# d150_in8-2_rev_a.net
KiCad netlist of a schematic drawn in EAGLE
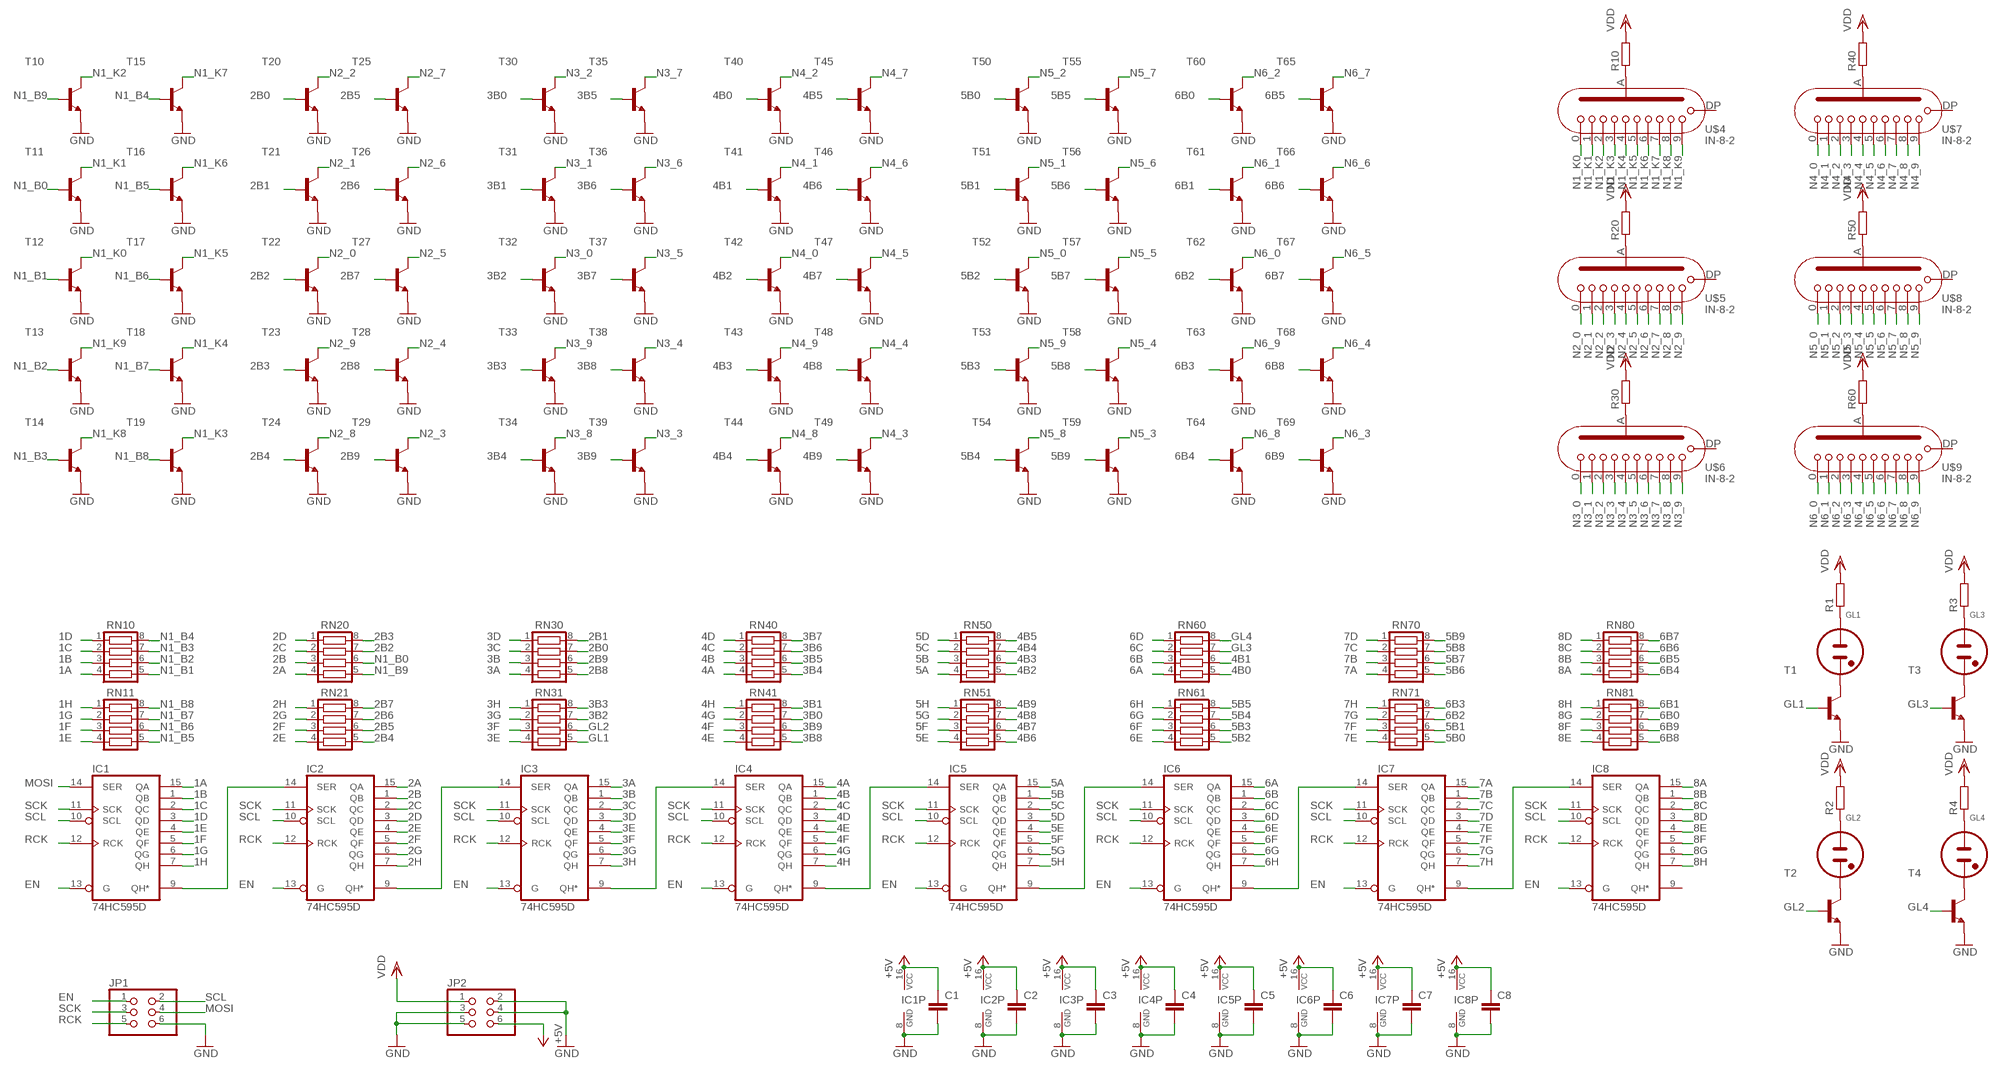
[diagram p0: schematic, sheet 1]

(export (version "E")
  (design (tool "Eeschema 10.0.6"))
  (components
    (comp (ref "C1")
      (value "C-EUC0603")
      (footprint "eagle-import:C0603")
      (libsource (lib "eagle-import") (part "C-EUC0603"))
    )
    (comp (ref "C2")
      (value "C-EUC0603")
      (footprint "eagle-import:C0603")
      (libsource (lib "eagle-import") (part "C-EUC0603"))
    )
    (comp (ref "C3")
      (value "C-EUC0603")
      (footprint "eagle-import:C0603")
      (libsource (lib "eagle-import") (part "C-EUC0603"))
    )
    (comp (ref "C4")
      (value "C-EUC0603")
      (footprint "eagle-import:C0603")
      (libsource (lib "eagle-import") (part "C-EUC0603"))
    )
    (comp (ref "C5")
      (value "C-EUC0603")
      (footprint "eagle-import:C0603")
      (libsource (lib "eagle-import") (part "C-EUC0603"))
    )
    (comp (ref "C6")
      (value "C-EUC0603")
      (footprint "eagle-import:C0603")
      (libsource (lib "eagle-import") (part "C-EUC0603"))
    )
    (comp (ref "C7")
      (value "C-EUC0603")
      (footprint "eagle-import:C0603")
      (libsource (lib "eagle-import") (part "C-EUC0603"))
    )
    (comp (ref "C8")
      (value "C-EUC0603")
      (footprint "eagle-import:C0603")
      (libsource (lib "eagle-import") (part "C-EUC0603"))
    )
    (comp (ref "GL1")
      (value "NE2-NEON-BULB-DRILL")
      (footprint "eagle-import:NE2-NEON-BULB-DRILL")
      (libsource (lib "eagle-import") (part "NE2-NEON-BULB-DRILL"))
    )
    (comp (ref "GL2")
      (value "NE2-NEON-BULB-DRILL")
      (footprint "eagle-import:NE2-NEON-BULB-DRILL")
      (libsource (lib "eagle-import") (part "NE2-NEON-BULB-DRILL"))
    )
    (comp (ref "GL3")
      (value "NE2-NEON-BULB-DRILL")
      (footprint "eagle-import:NE2-NEON-BULB-DRILL")
      (libsource (lib "eagle-import") (part "NE2-NEON-BULB-DRILL"))
    )
    (comp (ref "GL4")
      (value "NE2-NEON-BULB-DRILL")
      (footprint "eagle-import:NE2-NEON-BULB-DRILL")
      (libsource (lib "eagle-import") (part "NE2-NEON-BULB-DRILL"))
    )
    (comp (ref "IC1")
      (value "74HC595D")
      (footprint "eagle-import:SO16")
      (libsource (lib "eagle-import") (part "74595DHC"))
    )
    (comp (ref "IC2")
      (value "74HC595D")
      (footprint "eagle-import:SO16")
      (libsource (lib "eagle-import") (part "74595DHC"))
    )
    (comp (ref "IC3")
      (value "74HC595D")
      (footprint "eagle-import:SO16")
      (libsource (lib "eagle-import") (part "74595DHC"))
    )
    (comp (ref "IC4")
      (value "74HC595D")
      (footprint "eagle-import:SO16")
      (libsource (lib "eagle-import") (part "74595DHC"))
    )
    (comp (ref "IC5")
      (value "74HC595D")
      (footprint "eagle-import:SO16")
      (libsource (lib "eagle-import") (part "74595DHC"))
    )
    (comp (ref "IC6")
      (value "74HC595D")
      (footprint "eagle-import:SO16")
      (libsource (lib "eagle-import") (part "74595DHC"))
    )
    (comp (ref "IC7")
      (value "74HC595D")
      (footprint "eagle-import:SO16")
      (libsource (lib "eagle-import") (part "74595DHC"))
    )
    (comp (ref "IC8")
      (value "74HC595D")
      (footprint "eagle-import:SO16")
      (libsource (lib "eagle-import") (part "74595DHC"))
    )
    (comp (ref "JP1")
      (value "PINHD-2X3_2.54-SMD")
      (footprint "eagle-import:2X03SMD")
      (libsource (lib "eagle-import") (part "PINHD-2X3_2.54-SMD"))
    )
    (comp (ref "JP2")
      (value "PINHD-2X3_2.54-SMD")
      (footprint "eagle-import:2X03SMD")
      (libsource (lib "eagle-import") (part "PINHD-2X3_2.54-SMD"))
    )
    (comp (ref "R1")
      (value "R-EU_R0603")
      (footprint "eagle-import:R0603")
      (libsource (lib "eagle-import") (part "R-EU_R0603"))
    )
    (comp (ref "R2")
      (value "R-EU_R0603")
      (footprint "eagle-import:R0603")
      (libsource (lib "eagle-import") (part "R-EU_R0603"))
    )
    (comp (ref "R3")
      (value "R-EU_R0603")
      (footprint "eagle-import:R0603")
      (libsource (lib "eagle-import") (part "R-EU_R0603"))
    )
    (comp (ref "R4")
      (value "R-EU_R0603")
      (footprint "eagle-import:R0603")
      (libsource (lib "eagle-import") (part "R-EU_R0603"))
    )
    (comp (ref "R10")
      (value "R-EU_R0603")
      (footprint "eagle-import:R0603")
      (libsource (lib "eagle-import") (part "R-EU_R0603"))
    )
    (comp (ref "R20")
      (value "R-EU_R0603")
      (footprint "eagle-import:R0603")
      (libsource (lib "eagle-import") (part "R-EU_R0603"))
    )
    (comp (ref "R30")
      (value "R-EU_R0603")
      (footprint "eagle-import:R0603")
      (libsource (lib "eagle-import") (part "R-EU_R0603"))
    )
    (comp (ref "R40")
      (value "R-EU_R0603")
      (footprint "eagle-import:R0603")
      (libsource (lib "eagle-import") (part "R-EU_R0603"))
    )
    (comp (ref "R50")
      (value "R-EU_R0603")
      (footprint "eagle-import:R0603")
      (libsource (lib "eagle-import") (part "R-EU_R0603"))
    )
    (comp (ref "R60")
      (value "R-EU_R0603")
      (footprint "eagle-import:R0603")
      (libsource (lib "eagle-import") (part "R-EU_R0603"))
    )
    (comp (ref "RN10")
      (value "CTS742C083")
      (footprint "eagle-import:CTS742C083")
      (fields (field (name "OC_FARNELL") "unknown") (field (name "OC_NEWARK") "unknown"))
      (libsource (lib "eagle-import") (part "CTS742C083"))
    )
    (comp (ref "RN11")
      (value "CTS742C083")
      (footprint "eagle-import:CTS742C083")
      (fields (field (name "OC_FARNELL") "unknown") (field (name "OC_NEWARK") "unknown"))
      (libsource (lib "eagle-import") (part "CTS742C083"))
    )
    (comp (ref "RN20")
      (value "CTS742C083")
      (footprint "eagle-import:CTS742C083")
      (fields (field (name "OC_FARNELL") "unknown") (field (name "OC_NEWARK") "unknown"))
      (libsource (lib "eagle-import") (part "CTS742C083"))
    )
    (comp (ref "RN21")
      (value "CTS742C083")
      (footprint "eagle-import:CTS742C083")
      (fields (field (name "OC_FARNELL") "unknown") (field (name "OC_NEWARK") "unknown"))
      (libsource (lib "eagle-import") (part "CTS742C083"))
    )
    (comp (ref "RN30")
      (value "CTS742C083")
      (footprint "eagle-import:CTS742C083")
      (fields (field (name "OC_FARNELL") "unknown") (field (name "OC_NEWARK") "unknown"))
      (libsource (lib "eagle-import") (part "CTS742C083"))
    )
    (comp (ref "RN31")
      (value "CTS742C083")
      (footprint "eagle-import:CTS742C083")
      (fields (field (name "OC_FARNELL") "unknown") (field (name "OC_NEWARK") "unknown"))
      (libsource (lib "eagle-import") (part "CTS742C083"))
    )
    (comp (ref "RN40")
      (value "CTS742C083")
      (footprint "eagle-import:CTS742C083")
      (fields (field (name "OC_FARNELL") "unknown") (field (name "OC_NEWARK") "unknown"))
      (libsource (lib "eagle-import") (part "CTS742C083"))
    )
    (comp (ref "RN41")
      (value "CTS742C083")
      (footprint "eagle-import:CTS742C083")
      (fields (field (name "OC_FARNELL") "unknown") (field (name "OC_NEWARK") "unknown"))
      (libsource (lib "eagle-import") (part "CTS742C083"))
    )
    (comp (ref "RN50")
      (value "CTS742C083")
      (footprint "eagle-import:CTS742C083")
      (fields (field (name "OC_FARNELL") "unknown") (field (name "OC_NEWARK") "unknown"))
      (libsource (lib "eagle-import") (part "CTS742C083"))
    )
    (comp (ref "RN51")
      (value "CTS742C083")
      (footprint "eagle-import:CTS742C083")
      (fields (field (name "OC_FARNELL") "unknown") (field (name "OC_NEWARK") "unknown"))
      (libsource (lib "eagle-import") (part "CTS742C083"))
    )
    (comp (ref "RN60")
      (value "CTS742C083")
      (footprint "eagle-import:CTS742C083")
      (fields (field (name "OC_FARNELL") "unknown") (field (name "OC_NEWARK") "unknown"))
      (libsource (lib "eagle-import") (part "CTS742C083"))
    )
    (comp (ref "RN61")
      (value "CTS742C083")
      (footprint "eagle-import:CTS742C083")
      (fields (field (name "OC_FARNELL") "unknown") (field (name "OC_NEWARK") "unknown"))
      (libsource (lib "eagle-import") (part "CTS742C083"))
    )
    (comp (ref "RN70")
      (value "CTS742C083")
      (footprint "eagle-import:CTS742C083")
      (fields (field (name "OC_FARNELL") "unknown") (field (name "OC_NEWARK") "unknown"))
      (libsource (lib "eagle-import") (part "CTS742C083"))
    )
    (comp (ref "RN71")
      (value "CTS742C083")
      (footprint "eagle-import:CTS742C083")
      (fields (field (name "OC_FARNELL") "unknown") (field (name "OC_NEWARK") "unknown"))
      (libsource (lib "eagle-import") (part "CTS742C083"))
    )
    (comp (ref "RN80")
      (value "CTS742C083")
      (footprint "eagle-import:CTS742C083")
      (fields (field (name "OC_FARNELL") "unknown") (field (name "OC_NEWARK") "unknown"))
      (libsource (lib "eagle-import") (part "CTS742C083"))
    )
    (comp (ref "RN81")
      (value "CTS742C083")
      (footprint "eagle-import:CTS742C083")
      (fields (field (name "OC_FARNELL") "unknown") (field (name "OC_NEWARK") "unknown"))
      (libsource (lib "eagle-import") (part "CTS742C083"))
    )
    (comp (ref "T1")
      (value "SMBTA42")
      (footprint "eagle-import:SOT23")
      (libsource (lib "eagle-import") (part "SMBTA42"))
    )
    (comp (ref "T2")
      (value "SMBTA42")
      (footprint "eagle-import:SOT23")
      (libsource (lib "eagle-import") (part "SMBTA42"))
    )
    (comp (ref "T3")
      (value "SMBTA42")
      (footprint "eagle-import:SOT23")
      (libsource (lib "eagle-import") (part "SMBTA42"))
    )
    (comp (ref "T4")
      (value "SMBTA42")
      (footprint "eagle-import:SOT23")
      (libsource (lib "eagle-import") (part "SMBTA42"))
    )
    (comp (ref "T10")
      (value "SMBTA42")
      (footprint "eagle-import:SOT23")
      (libsource (lib "eagle-import") (part "SMBTA42"))
    )
    (comp (ref "T11")
      (value "SMBTA42")
      (footprint "eagle-import:SOT23")
      (libsource (lib "eagle-import") (part "SMBTA42"))
    )
    (comp (ref "T12")
      (value "SMBTA42")
      (footprint "eagle-import:SOT23")
      (libsource (lib "eagle-import") (part "SMBTA42"))
    )
    (comp (ref "T13")
      (value "SMBTA42")
      (footprint "eagle-import:SOT23")
      (libsource (lib "eagle-import") (part "SMBTA42"))
    )
    (comp (ref "T14")
      (value "SMBTA42")
      (footprint "eagle-import:SOT23")
      (libsource (lib "eagle-import") (part "SMBTA42"))
    )
    (comp (ref "T15")
      (value "SMBTA42")
      (footprint "eagle-import:SOT23")
      (libsource (lib "eagle-import") (part "SMBTA42"))
    )
    (comp (ref "T16")
      (value "SMBTA42")
      (footprint "eagle-import:SOT23")
      (libsource (lib "eagle-import") (part "SMBTA42"))
    )
    (comp (ref "T17")
      (value "SMBTA42")
      (footprint "eagle-import:SOT23")
      (libsource (lib "eagle-import") (part "SMBTA42"))
    )
    (comp (ref "T18")
      (value "SMBTA42")
      (footprint "eagle-import:SOT23")
      (libsource (lib "eagle-import") (part "SMBTA42"))
    )
    (comp (ref "T19")
      (value "SMBTA42")
      (footprint "eagle-import:SOT23")
      (libsource (lib "eagle-import") (part "SMBTA42"))
    )
    (comp (ref "T20")
      (value "SMBTA42")
      (footprint "eagle-import:SOT23")
      (libsource (lib "eagle-import") (part "SMBTA42"))
    )
    (comp (ref "T21")
      (value "SMBTA42")
      (footprint "eagle-import:SOT23")
      (libsource (lib "eagle-import") (part "SMBTA42"))
    )
    (comp (ref "T22")
      (value "SMBTA42")
      (footprint "eagle-import:SOT23")
      (libsource (lib "eagle-import") (part "SMBTA42"))
    )
    (comp (ref "T23")
      (value "SMBTA42")
      (footprint "eagle-import:SOT23")
      (libsource (lib "eagle-import") (part "SMBTA42"))
    )
    (comp (ref "T24")
      (value "SMBTA42")
      (footprint "eagle-import:SOT23")
      (libsource (lib "eagle-import") (part "SMBTA42"))
    )
    (comp (ref "T25")
      (value "SMBTA42")
      (footprint "eagle-import:SOT23")
      (libsource (lib "eagle-import") (part "SMBTA42"))
    )
    (comp (ref "T26")
      (value "SMBTA42")
      (footprint "eagle-import:SOT23")
      (libsource (lib "eagle-import") (part "SMBTA42"))
    )
    (comp (ref "T27")
      (value "SMBTA42")
      (footprint "eagle-import:SOT23")
      (libsource (lib "eagle-import") (part "SMBTA42"))
    )
    (comp (ref "T28")
      (value "SMBTA42")
      (footprint "eagle-import:SOT23")
      (libsource (lib "eagle-import") (part "SMBTA42"))
    )
    (comp (ref "T29")
      (value "SMBTA42")
      (footprint "eagle-import:SOT23")
      (libsource (lib "eagle-import") (part "SMBTA42"))
    )
    (comp (ref "T30")
      (value "SMBTA42")
      (footprint "eagle-import:SOT23")
      (libsource (lib "eagle-import") (part "SMBTA42"))
    )
    (comp (ref "T31")
      (value "SMBTA42")
      (footprint "eagle-import:SOT23")
      (libsource (lib "eagle-import") (part "SMBTA42"))
    )
    (comp (ref "T32")
      (value "SMBTA42")
      (footprint "eagle-import:SOT23")
      (libsource (lib "eagle-import") (part "SMBTA42"))
    )
    (comp (ref "T33")
      (value "SMBTA42")
      (footprint "eagle-import:SOT23")
      (libsource (lib "eagle-import") (part "SMBTA42"))
    )
    (comp (ref "T34")
      (value "SMBTA42")
      (footprint "eagle-import:SOT23")
      (libsource (lib "eagle-import") (part "SMBTA42"))
    )
    (comp (ref "T35")
      (value "SMBTA42")
      (footprint "eagle-import:SOT23")
      (libsource (lib "eagle-import") (part "SMBTA42"))
    )
    (comp (ref "T36")
      (value "SMBTA42")
      (footprint "eagle-import:SOT23")
      (libsource (lib "eagle-import") (part "SMBTA42"))
    )
    (comp (ref "T37")
      (value "SMBTA42")
      (footprint "eagle-import:SOT23")
      (libsource (lib "eagle-import") (part "SMBTA42"))
    )
    (comp (ref "T38")
      (value "SMBTA42")
      (footprint "eagle-import:SOT23")
      (libsource (lib "eagle-import") (part "SMBTA42"))
    )
    (comp (ref "T39")
      (value "SMBTA42")
      (footprint "eagle-import:SOT23")
      (libsource (lib "eagle-import") (part "SMBTA42"))
    )
    (comp (ref "T40")
      (value "SMBTA42")
      (footprint "eagle-import:SOT23")
      (libsource (lib "eagle-import") (part "SMBTA42"))
    )
    (comp (ref "T41")
      (value "SMBTA42")
      (footprint "eagle-import:SOT23")
      (libsource (lib "eagle-import") (part "SMBTA42"))
    )
    (comp (ref "T42")
      (value "SMBTA42")
      (footprint "eagle-import:SOT23")
      (libsource (lib "eagle-import") (part "SMBTA42"))
    )
    (comp (ref "T43")
      (value "SMBTA42")
      (footprint "eagle-import:SOT23")
      (libsource (lib "eagle-import") (part "SMBTA42"))
    )
    (comp (ref "T44")
      (value "SMBTA42")
      (footprint "eagle-import:SOT23")
      (libsource (lib "eagle-import") (part "SMBTA42"))
    )
    (comp (ref "T45")
      (value "SMBTA42")
      (footprint "eagle-import:SOT23")
      (libsource (lib "eagle-import") (part "SMBTA42"))
    )
    (comp (ref "T46")
      (value "SMBTA42")
      (footprint "eagle-import:SOT23")
      (libsource (lib "eagle-import") (part "SMBTA42"))
    )
    (comp (ref "T47")
      (value "SMBTA42")
      (footprint "eagle-import:SOT23")
      (libsource (lib "eagle-import") (part "SMBTA42"))
    )
    (comp (ref "T48")
      (value "SMBTA42")
      (footprint "eagle-import:SOT23")
      (libsource (lib "eagle-import") (part "SMBTA42"))
    )
    (comp (ref "T49")
      (value "SMBTA42")
      (footprint "eagle-import:SOT23")
      (libsource (lib "eagle-import") (part "SMBTA42"))
    )
    (comp (ref "T50")
      (value "SMBTA42")
      (footprint "eagle-import:SOT23")
      (libsource (lib "eagle-import") (part "SMBTA42"))
    )
    (comp (ref "T51")
      (value "SMBTA42")
      (footprint "eagle-import:SOT23")
      (libsource (lib "eagle-import") (part "SMBTA42"))
    )
    (comp (ref "T52")
      (value "SMBTA42")
      (footprint "eagle-import:SOT23")
      (libsource (lib "eagle-import") (part "SMBTA42"))
    )
    (comp (ref "T53")
      (value "SMBTA42")
      (footprint "eagle-import:SOT23")
      (libsource (lib "eagle-import") (part "SMBTA42"))
    )
    (comp (ref "T54")
      (value "SMBTA42")
      (footprint "eagle-import:SOT23")
      (libsource (lib "eagle-import") (part "SMBTA42"))
    )
    (comp (ref "T55")
      (value "SMBTA42")
      (footprint "eagle-import:SOT23")
      (libsource (lib "eagle-import") (part "SMBTA42"))
    )
    (comp (ref "T56")
      (value "SMBTA42")
      (footprint "eagle-import:SOT23")
      (libsource (lib "eagle-import") (part "SMBTA42"))
    )
    (comp (ref "T57")
      (value "SMBTA42")
      (footprint "eagle-import:SOT23")
      (libsource (lib "eagle-import") (part "SMBTA42"))
    )
    (comp (ref "T58")
      (value "SMBTA42")
      (footprint "eagle-import:SOT23")
      (libsource (lib "eagle-import") (part "SMBTA42"))
    )
    (comp (ref "T59")
      (value "SMBTA42")
      (footprint "eagle-import:SOT23")
      (libsource (lib "eagle-import") (part "SMBTA42"))
    )
    (comp (ref "T60")
      (value "SMBTA42")
      (footprint "eagle-import:SOT23")
      (libsource (lib "eagle-import") (part "SMBTA42"))
    )
    (comp (ref "T61")
      (value "SMBTA42")
      (footprint "eagle-import:SOT23")
      (libsource (lib "eagle-import") (part "SMBTA42"))
    )
    (comp (ref "T62")
      (value "SMBTA42")
      (footprint "eagle-import:SOT23")
      (libsource (lib "eagle-import") (part "SMBTA42"))
    )
    (comp (ref "T63")
      (value "SMBTA42")
      (footprint "eagle-import:SOT23")
      (libsource (lib "eagle-import") (part "SMBTA42"))
    )
    (comp (ref "T64")
      (value "SMBTA42")
      (footprint "eagle-import:SOT23")
      (libsource (lib "eagle-import") (part "SMBTA42"))
    )
    (comp (ref "T65")
      (value "SMBTA42")
      (footprint "eagle-import:SOT23")
      (libsource (lib "eagle-import") (part "SMBTA42"))
    )
    (comp (ref "T66")
      (value "SMBTA42")
      (footprint "eagle-import:SOT23")
      (libsource (lib "eagle-import") (part "SMBTA42"))
    )
    (comp (ref "T67")
      (value "SMBTA42")
      (footprint "eagle-import:SOT23")
      (libsource (lib "eagle-import") (part "SMBTA42"))
    )
    (comp (ref "T68")
      (value "SMBTA42")
      (footprint "eagle-import:SOT23")
      (libsource (lib "eagle-import") (part "SMBTA42"))
    )
    (comp (ref "T69")
      (value "SMBTA42")
      (footprint "eagle-import:SOT23")
      (libsource (lib "eagle-import") (part "SMBTA42"))
    )
    (comp (ref "U$4")
      (value "IN-8-2")
      (footprint "eagle-import:IN-8-2")
      (libsource (lib "eagle-import") (part "IN-8-2"))
    )
    (comp (ref "U$5")
      (value "IN-8-2")
      (footprint "eagle-import:IN-8-2")
      (libsource (lib "eagle-import") (part "IN-8-2"))
    )
    (comp (ref "U$6")
      (value "IN-8-2")
      (footprint "eagle-import:IN-8-2")
      (libsource (lib "eagle-import") (part "IN-8-2"))
    )
    (comp (ref "U$7")
      (value "IN-8-2")
      (footprint "eagle-import:IN-8-2")
      (libsource (lib "eagle-import") (part "IN-8-2"))
    )
    (comp (ref "U$8")
      (value "IN-8-2")
      (footprint "eagle-import:IN-8-2")
      (libsource (lib "eagle-import") (part "IN-8-2"))
    )
    (comp (ref "U$9")
      (value "IN-8-2")
      (footprint "eagle-import:IN-8-2")
      (libsource (lib "eagle-import") (part "IN-8-2"))
    )
  )
  (nets
    (net (code "1") (name "+5V") (class "Default")
      (node (ref "C1") (pin "1") (pinfunction "1_1") (pintype "passive"))
      (node (ref "C2") (pin "1") (pinfunction "1_1") (pintype "passive"))
      (node (ref "C3") (pin "1") (pinfunction "1_1") (pintype "passive"))
      (node (ref "C4") (pin "1") (pinfunction "1_1") (pintype "passive"))
      (node (ref "C5") (pin "1") (pinfunction "1_1") (pintype "passive"))
      (node (ref "C6") (pin "1") (pinfunction "1_1") (pintype "passive"))
      (node (ref "C7") (pin "1") (pinfunction "1_1") (pintype "passive"))
      (node (ref "C8") (pin "1") (pinfunction "1_1") (pintype "passive"))
      (node (ref "IC1") (pin "16") (pinfunction "VCC_16") (pintype "power_in"))
      (node (ref "IC2") (pin "16") (pinfunction "VCC_16") (pintype "power_in"))
      (node (ref "IC3") (pin "16") (pinfunction "VCC_16") (pintype "power_in"))
      (node (ref "IC4") (pin "16") (pinfunction "VCC_16") (pintype "power_in"))
      (node (ref "IC5") (pin "16") (pinfunction "VCC_16") (pintype "power_in"))
      (node (ref "IC6") (pin "16") (pinfunction "VCC_16") (pintype "power_in"))
      (node (ref "IC7") (pin "16") (pinfunction "VCC_16") (pintype "power_in"))
      (node (ref "IC8") (pin "16") (pinfunction "VCC_16") (pintype "power_in"))
      (node (ref "JP2") (pin "6") (pinfunction "6_6") (pintype "passive"))
    )
    (net (code "2") (name "/1A") (class "Default")
      (node (ref "IC1") (pin "15") (pinfunction "QA_15") (pintype "tri_state"))
      (node (ref "RN10") (pin "4") (pinfunction "4_4") (pintype "passive"))
    )
    (net (code "3") (name "/1B") (class "Default")
      (node (ref "IC1") (pin "1") (pinfunction "QB_1") (pintype "tri_state"))
      (node (ref "RN10") (pin "3") (pinfunction "3_3") (pintype "passive"))
    )
    (net (code "4") (name "/1C") (class "Default")
      (node (ref "IC1") (pin "2") (pinfunction "QC_2") (pintype "tri_state"))
      (node (ref "RN10") (pin "2") (pinfunction "2_2") (pintype "passive"))
    )
    (net (code "5") (name "/1D") (class "Default")
      (node (ref "IC1") (pin "3") (pinfunction "QD_3") (pintype "tri_state"))
      (node (ref "RN10") (pin "1") (pinfunction "1_1") (pintype "passive"))
    )
    (net (code "6") (name "/1E") (class "Default")
      (node (ref "IC1") (pin "4") (pinfunction "QE_4") (pintype "tri_state"))
      (node (ref "RN11") (pin "4") (pinfunction "4_4") (pintype "passive"))
    )
    (net (code "7") (name "/1F") (class "Default")
      (node (ref "IC1") (pin "5") (pinfunction "QF_5") (pintype "tri_state"))
      (node (ref "RN11") (pin "3") (pinfunction "3_3") (pintype "passive"))
    )
    (net (code "8") (name "/1G") (class "Default")
      (node (ref "IC1") (pin "6") (pinfunction "QG_6") (pintype "tri_state"))
      (node (ref "RN11") (pin "2") (pinfunction "2_2") (pintype "passive"))
    )
    (net (code "9") (name "/1H") (class "Default")
      (node (ref "IC1") (pin "7") (pinfunction "QH_7") (pintype "tri_state"))
      (node (ref "RN11") (pin "1") (pinfunction "1_1") (pintype "passive"))
    )
    (net (code "10") (name "/2A") (class "Default")
      (node (ref "IC2") (pin "15") (pinfunction "QA_15") (pintype "tri_state"))
      (node (ref "RN20") (pin "4") (pinfunction "4_4") (pintype "passive"))
    )
    (net (code "11") (name "/2B") (class "Default")
      (node (ref "IC2") (pin "1") (pinfunction "QB_1") (pintype "tri_state"))
      (node (ref "RN20") (pin "3") (pinfunction "3_3") (pintype "passive"))
    )
    (net (code "12") (name "/2B0") (class "Default")
      (node (ref "RN30") (pin "7") (pinfunction "7_7") (pintype "passive"))
      (node (ref "T20") (pin "1") (pinfunction "B_1") (pintype "passive"))
    )
    (net (code "13") (name "/2B1") (class "Default")
      (node (ref "RN30") (pin "8") (pinfunction "8_8") (pintype "passive"))
      (node (ref "T21") (pin "1") (pinfunction "B_1") (pintype "passive"))
    )
    (net (code "14") (name "/2B2") (class "Default")
      (node (ref "RN20") (pin "7") (pinfunction "7_7") (pintype "passive"))
      (node (ref "T22") (pin "1") (pinfunction "B_1") (pintype "passive"))
    )
    (net (code "15") (name "/2B3") (class "Default")
      (node (ref "RN20") (pin "8") (pinfunction "8_8") (pintype "passive"))
      (node (ref "T23") (pin "1") (pinfunction "B_1") (pintype "passive"))
    )
    (net (code "16") (name "/2B4") (class "Default")
      (node (ref "RN21") (pin "5") (pinfunction "5_5") (pintype "passive"))
      (node (ref "T24") (pin "1") (pinfunction "B_1") (pintype "passive"))
    )
    (net (code "17") (name "/2B5") (class "Default")
      (node (ref "RN21") (pin "6") (pinfunction "6_6") (pintype "passive"))
      (node (ref "T25") (pin "1") (pinfunction "B_1") (pintype "passive"))
    )
    (net (code "18") (name "/2B6") (class "Default")
      (node (ref "RN21") (pin "7") (pinfunction "7_7") (pintype "passive"))
      (node (ref "T26") (pin "1") (pinfunction "B_1") (pintype "passive"))
    )
    (net (code "19") (name "/2B7") (class "Default")
      (node (ref "RN21") (pin "8") (pinfunction "8_8") (pintype "passive"))
      (node (ref "T27") (pin "1") (pinfunction "B_1") (pintype "passive"))
    )
    (net (code "20") (name "/2B8") (class "Default")
      (node (ref "RN30") (pin "5") (pinfunction "5_5") (pintype "passive"))
      (node (ref "T28") (pin "1") (pinfunction "B_1") (pintype "passive"))
    )
    (net (code "21") (name "/2B9") (class "Default")
      (node (ref "RN30") (pin "6") (pinfunction "6_6") (pintype "passive"))
      (node (ref "T29") (pin "1") (pinfunction "B_1") (pintype "passive"))
    )
    (net (code "22") (name "/2C") (class "Default")
      (node (ref "IC2") (pin "2") (pinfunction "QC_2") (pintype "tri_state"))
      (node (ref "RN20") (pin "2") (pinfunction "2_2") (pintype "passive"))
    )
    (net (code "23") (name "/2D") (class "Default")
      (node (ref "IC2") (pin "3") (pinfunction "QD_3") (pintype "tri_state"))
      (node (ref "RN20") (pin "1") (pinfunction "1_1") (pintype "passive"))
    )
    (net (code "24") (name "/2E") (class "Default")
      (node (ref "IC2") (pin "4") (pinfunction "QE_4") (pintype "tri_state"))
      (node (ref "RN21") (pin "4") (pinfunction "4_4") (pintype "passive"))
    )
    (net (code "25") (name "/2F") (class "Default")
      (node (ref "IC2") (pin "5") (pinfunction "QF_5") (pintype "tri_state"))
      (node (ref "RN21") (pin "3") (pinfunction "3_3") (pintype "passive"))
    )
    (net (code "26") (name "/2G") (class "Default")
      (node (ref "IC2") (pin "6") (pinfunction "QG_6") (pintype "tri_state"))
      (node (ref "RN21") (pin "2") (pinfunction "2_2") (pintype "passive"))
    )
    (net (code "27") (name "/2H") (class "Default")
      (node (ref "IC2") (pin "7") (pinfunction "QH_7") (pintype "tri_state"))
      (node (ref "RN21") (pin "1") (pinfunction "1_1") (pintype "passive"))
    )
    (net (code "28") (name "/3A") (class "Default")
      (node (ref "IC3") (pin "15") (pinfunction "QA_15") (pintype "tri_state"))
      (node (ref "RN30") (pin "4") (pinfunction "4_4") (pintype "passive"))
    )
    (net (code "29") (name "/3B") (class "Default")
      (node (ref "IC3") (pin "1") (pinfunction "QB_1") (pintype "tri_state"))
      (node (ref "RN30") (pin "3") (pinfunction "3_3") (pintype "passive"))
    )
    (net (code "30") (name "/3B0") (class "Default")
      (node (ref "RN41") (pin "7") (pinfunction "7_7") (pintype "passive"))
      (node (ref "T30") (pin "1") (pinfunction "B_1") (pintype "passive"))
    )
    (net (code "31") (name "/3B1") (class "Default")
      (node (ref "RN41") (pin "8") (pinfunction "8_8") (pintype "passive"))
      (node (ref "T31") (pin "1") (pinfunction "B_1") (pintype "passive"))
    )
    (net (code "32") (name "/3B2") (class "Default")
      (node (ref "RN31") (pin "7") (pinfunction "7_7") (pintype "passive"))
      (node (ref "T32") (pin "1") (pinfunction "B_1") (pintype "passive"))
    )
    (net (code "33") (name "/3B3") (class "Default")
      (node (ref "RN31") (pin "8") (pinfunction "8_8") (pintype "passive"))
      (node (ref "T33") (pin "1") (pinfunction "B_1") (pintype "passive"))
    )
    (net (code "34") (name "/3B4") (class "Default")
      (node (ref "RN40") (pin "5") (pinfunction "5_5") (pintype "passive"))
      (node (ref "T34") (pin "1") (pinfunction "B_1") (pintype "passive"))
    )
    (net (code "35") (name "/3B5") (class "Default")
      (node (ref "RN40") (pin "6") (pinfunction "6_6") (pintype "passive"))
      (node (ref "T35") (pin "1") (pinfunction "B_1") (pintype "passive"))
    )
    (net (code "36") (name "/3B6") (class "Default")
      (node (ref "RN40") (pin "7") (pinfunction "7_7") (pintype "passive"))
      (node (ref "T36") (pin "1") (pinfunction "B_1") (pintype "passive"))
    )
    (net (code "37") (name "/3B7") (class "Default")
      (node (ref "RN40") (pin "8") (pinfunction "8_8") (pintype "passive"))
      (node (ref "T37") (pin "1") (pinfunction "B_1") (pintype "passive"))
    )
    (net (code "38") (name "/3B8") (class "Default")
      (node (ref "RN41") (pin "5") (pinfunction "5_5") (pintype "passive"))
      (node (ref "T38") (pin "1") (pinfunction "B_1") (pintype "passive"))
    )
    (net (code "39") (name "/3B9") (class "Default")
      (node (ref "RN41") (pin "6") (pinfunction "6_6") (pintype "passive"))
      (node (ref "T39") (pin "1") (pinfunction "B_1") (pintype "passive"))
    )
    (net (code "40") (name "/3C") (class "Default")
      (node (ref "IC3") (pin "2") (pinfunction "QC_2") (pintype "tri_state"))
      (node (ref "RN30") (pin "2") (pinfunction "2_2") (pintype "passive"))
    )
    (net (code "41") (name "/3D") (class "Default")
      (node (ref "IC3") (pin "3") (pinfunction "QD_3") (pintype "tri_state"))
      (node (ref "RN30") (pin "1") (pinfunction "1_1") (pintype "passive"))
    )
    (net (code "42") (name "/3E") (class "Default")
      (node (ref "IC3") (pin "4") (pinfunction "QE_4") (pintype "tri_state"))
      (node (ref "RN31") (pin "4") (pinfunction "4_4") (pintype "passive"))
    )
    (net (code "43") (name "/3F") (class "Default")
      (node (ref "IC3") (pin "5") (pinfunction "QF_5") (pintype "tri_state"))
      (node (ref "RN31") (pin "3") (pinfunction "3_3") (pintype "passive"))
    )
    (net (code "44") (name "/3G") (class "Default")
      (node (ref "IC3") (pin "6") (pinfunction "QG_6") (pintype "tri_state"))
      (node (ref "RN31") (pin "2") (pinfunction "2_2") (pintype "passive"))
    )
    (net (code "45") (name "/3H") (class "Default")
      (node (ref "IC3") (pin "7") (pinfunction "QH_7") (pintype "tri_state"))
      (node (ref "RN31") (pin "1") (pinfunction "1_1") (pintype "passive"))
    )
    (net (code "46") (name "/4A") (class "Default")
      (node (ref "IC4") (pin "15") (pinfunction "QA_15") (pintype "tri_state"))
      (node (ref "RN40") (pin "4") (pinfunction "4_4") (pintype "passive"))
    )
    (net (code "47") (name "/4B") (class "Default")
      (node (ref "IC4") (pin "1") (pinfunction "QB_1") (pintype "tri_state"))
      (node (ref "RN40") (pin "3") (pinfunction "3_3") (pintype "passive"))
    )
    (net (code "48") (name "/4B0") (class "Default")
      (node (ref "RN60") (pin "5") (pinfunction "5_5") (pintype "passive"))
      (node (ref "T40") (pin "1") (pinfunction "B_1") (pintype "passive"))
    )
    (net (code "49") (name "/4B1") (class "Default")
      (node (ref "RN60") (pin "6") (pinfunction "6_6") (pintype "passive"))
      (node (ref "T41") (pin "1") (pinfunction "B_1") (pintype "passive"))
    )
    (net (code "50") (name "/4B2") (class "Default")
      (node (ref "RN50") (pin "5") (pinfunction "5_5") (pintype "passive"))
      (node (ref "T42") (pin "1") (pinfunction "B_1") (pintype "passive"))
    )
    (net (code "51") (name "/4B3") (class "Default")
      (node (ref "RN50") (pin "6") (pinfunction "6_6") (pintype "passive"))
      (node (ref "T43") (pin "1") (pinfunction "B_1") (pintype "passive"))
    )
    (net (code "52") (name "/4B4") (class "Default")
      (node (ref "RN50") (pin "7") (pinfunction "7_7") (pintype "passive"))
      (node (ref "T44") (pin "1") (pinfunction "B_1") (pintype "passive"))
    )
    (net (code "53") (name "/4B5") (class "Default")
      (node (ref "RN50") (pin "8") (pinfunction "8_8") (pintype "passive"))
      (node (ref "T45") (pin "1") (pinfunction "B_1") (pintype "passive"))
    )
    (net (code "54") (name "/4B6") (class "Default")
      (node (ref "RN51") (pin "5") (pinfunction "5_5") (pintype "passive"))
      (node (ref "T46") (pin "1") (pinfunction "B_1") (pintype "passive"))
    )
    (net (code "55") (name "/4B7") (class "Default")
      (node (ref "RN51") (pin "6") (pinfunction "6_6") (pintype "passive"))
      (node (ref "T47") (pin "1") (pinfunction "B_1") (pintype "passive"))
    )
    (net (code "56") (name "/4B8") (class "Default")
      (node (ref "RN51") (pin "7") (pinfunction "7_7") (pintype "passive"))
      (node (ref "T48") (pin "1") (pinfunction "B_1") (pintype "passive"))
    )
    (net (code "57") (name "/4B9") (class "Default")
      (node (ref "RN51") (pin "8") (pinfunction "8_8") (pintype "passive"))
      (node (ref "T49") (pin "1") (pinfunction "B_1") (pintype "passive"))
    )
    (net (code "58") (name "/4C") (class "Default")
      (node (ref "IC4") (pin "2") (pinfunction "QC_2") (pintype "tri_state"))
      (node (ref "RN40") (pin "2") (pinfunction "2_2") (pintype "passive"))
    )
    (net (code "59") (name "/4D") (class "Default")
      (node (ref "IC4") (pin "3") (pinfunction "QD_3") (pintype "tri_state"))
      (node (ref "RN40") (pin "1") (pinfunction "1_1") (pintype "passive"))
    )
    (net (code "60") (name "/4E") (class "Default")
      (node (ref "IC4") (pin "4") (pinfunction "QE_4") (pintype "tri_state"))
      (node (ref "RN41") (pin "4") (pinfunction "4_4") (pintype "passive"))
    )
    (net (code "61") (name "/4F") (class "Default")
      (node (ref "IC4") (pin "5") (pinfunction "QF_5") (pintype "tri_state"))
      (node (ref "RN41") (pin "3") (pinfunction "3_3") (pintype "passive"))
    )
    (net (code "62") (name "/4G") (class "Default")
      (node (ref "IC4") (pin "6") (pinfunction "QG_6") (pintype "tri_state"))
      (node (ref "RN41") (pin "2") (pinfunction "2_2") (pintype "passive"))
    )
    (net (code "63") (name "/4H") (class "Default")
      (node (ref "IC4") (pin "7") (pinfunction "QH_7") (pintype "tri_state"))
      (node (ref "RN41") (pin "1") (pinfunction "1_1") (pintype "passive"))
    )
    (net (code "64") (name "/5A") (class "Default")
      (node (ref "IC5") (pin "15") (pinfunction "QA_15") (pintype "tri_state"))
      (node (ref "RN50") (pin "4") (pinfunction "4_4") (pintype "passive"))
    )
    (net (code "65") (name "/5B") (class "Default")
      (node (ref "IC5") (pin "1") (pinfunction "QB_1") (pintype "tri_state"))
      (node (ref "RN50") (pin "3") (pinfunction "3_3") (pintype "passive"))
    )
    (net (code "66") (name "/5B0") (class "Default")
      (node (ref "RN71") (pin "5") (pinfunction "5_5") (pintype "passive"))
      (node (ref "T50") (pin "1") (pinfunction "B_1") (pintype "passive"))
    )
    (net (code "67") (name "/5B1") (class "Default")
      (node (ref "RN71") (pin "6") (pinfunction "6_6") (pintype "passive"))
      (node (ref "T51") (pin "1") (pinfunction "B_1") (pintype "passive"))
    )
    (net (code "68") (name "/5B2") (class "Default")
      (node (ref "RN61") (pin "5") (pinfunction "5_5") (pintype "passive"))
      (node (ref "T52") (pin "1") (pinfunction "B_1") (pintype "passive"))
    )
    (net (code "69") (name "/5B3") (class "Default")
      (node (ref "RN61") (pin "6") (pinfunction "6_6") (pintype "passive"))
      (node (ref "T53") (pin "1") (pinfunction "B_1") (pintype "passive"))
    )
    (net (code "70") (name "/5B4") (class "Default")
      (node (ref "RN61") (pin "7") (pinfunction "7_7") (pintype "passive"))
      (node (ref "T54") (pin "1") (pinfunction "B_1") (pintype "passive"))
    )
    (net (code "71") (name "/5B5") (class "Default")
      (node (ref "RN61") (pin "8") (pinfunction "8_8") (pintype "passive"))
      (node (ref "T55") (pin "1") (pinfunction "B_1") (pintype "passive"))
    )
    (net (code "72") (name "/5B6") (class "Default")
      (node (ref "RN70") (pin "5") (pinfunction "5_5") (pintype "passive"))
      (node (ref "T56") (pin "1") (pinfunction "B_1") (pintype "passive"))
    )
    (net (code "73") (name "/5B7") (class "Default")
      (node (ref "RN70") (pin "6") (pinfunction "6_6") (pintype "passive"))
      (node (ref "T57") (pin "1") (pinfunction "B_1") (pintype "passive"))
    )
    (net (code "74") (name "/5B8") (class "Default")
      (node (ref "RN70") (pin "7") (pinfunction "7_7") (pintype "passive"))
      (node (ref "T58") (pin "1") (pinfunction "B_1") (pintype "passive"))
    )
    (net (code "75") (name "/5B9") (class "Default")
      (node (ref "RN70") (pin "8") (pinfunction "8_8") (pintype "passive"))
      (node (ref "T59") (pin "1") (pinfunction "B_1") (pintype "passive"))
    )
    (net (code "76") (name "/5C") (class "Default")
      (node (ref "IC5") (pin "2") (pinfunction "QC_2") (pintype "tri_state"))
      (node (ref "RN50") (pin "2") (pinfunction "2_2") (pintype "passive"))
    )
    (net (code "77") (name "/5D") (class "Default")
      (node (ref "IC5") (pin "3") (pinfunction "QD_3") (pintype "tri_state"))
      (node (ref "RN50") (pin "1") (pinfunction "1_1") (pintype "passive"))
    )
    (net (code "78") (name "/5E") (class "Default")
      (node (ref "IC5") (pin "4") (pinfunction "QE_4") (pintype "tri_state"))
      (node (ref "RN51") (pin "4") (pinfunction "4_4") (pintype "passive"))
    )
    (net (code "79") (name "/5F") (class "Default")
      (node (ref "IC5") (pin "5") (pinfunction "QF_5") (pintype "tri_state"))
      (node (ref "RN51") (pin "3") (pinfunction "3_3") (pintype "passive"))
    )
    (net (code "80") (name "/5G") (class "Default")
      (node (ref "IC5") (pin "6") (pinfunction "QG_6") (pintype "tri_state"))
      (node (ref "RN51") (pin "2") (pinfunction "2_2") (pintype "passive"))
    )
    (net (code "81") (name "/5H") (class "Default")
      (node (ref "IC5") (pin "7") (pinfunction "QH_7") (pintype "tri_state"))
      (node (ref "RN51") (pin "1") (pinfunction "1_1") (pintype "passive"))
    )
    (net (code "82") (name "/6A") (class "Default")
      (node (ref "IC6") (pin "15") (pinfunction "QA_15") (pintype "tri_state"))
      (node (ref "RN60") (pin "4") (pinfunction "4_4") (pintype "passive"))
    )
    (net (code "83") (name "/6B") (class "Default")
      (node (ref "IC6") (pin "1") (pinfunction "QB_1") (pintype "tri_state"))
      (node (ref "RN60") (pin "3") (pinfunction "3_3") (pintype "passive"))
    )
    (net (code "84") (name "/6B0") (class "Default")
      (node (ref "RN81") (pin "7") (pinfunction "7_7") (pintype "passive"))
      (node (ref "T60") (pin "1") (pinfunction "B_1") (pintype "passive"))
    )
    (net (code "85") (name "/6B1") (class "Default")
      (node (ref "RN81") (pin "8") (pinfunction "8_8") (pintype "passive"))
      (node (ref "T61") (pin "1") (pinfunction "B_1") (pintype "passive"))
    )
    (net (code "86") (name "/6B2") (class "Default")
      (node (ref "RN71") (pin "7") (pinfunction "7_7") (pintype "passive"))
      (node (ref "T62") (pin "1") (pinfunction "B_1") (pintype "passive"))
    )
    (net (code "87") (name "/6B3") (class "Default")
      (node (ref "RN71") (pin "8") (pinfunction "8_8") (pintype "passive"))
      (node (ref "T63") (pin "1") (pinfunction "B_1") (pintype "passive"))
    )
    (net (code "88") (name "/6B4") (class "Default")
      (node (ref "RN80") (pin "5") (pinfunction "5_5") (pintype "passive"))
      (node (ref "T64") (pin "1") (pinfunction "B_1") (pintype "passive"))
    )
    (net (code "89") (name "/6B5") (class "Default")
      (node (ref "RN80") (pin "6") (pinfunction "6_6") (pintype "passive"))
      (node (ref "T65") (pin "1") (pinfunction "B_1") (pintype "passive"))
    )
    (net (code "90") (name "/6B6") (class "Default")
      (node (ref "RN80") (pin "7") (pinfunction "7_7") (pintype "passive"))
      (node (ref "T66") (pin "1") (pinfunction "B_1") (pintype "passive"))
    )
    (net (code "91") (name "/6B7") (class "Default")
      (node (ref "RN80") (pin "8") (pinfunction "8_8") (pintype "passive"))
      (node (ref "T67") (pin "1") (pinfunction "B_1") (pintype "passive"))
    )
    (net (code "92") (name "/6B8") (class "Default")
      (node (ref "RN81") (pin "5") (pinfunction "5_5") (pintype "passive"))
      (node (ref "T68") (pin "1") (pinfunction "B_1") (pintype "passive"))
    )
    (net (code "93") (name "/6B9") (class "Default")
      (node (ref "RN81") (pin "6") (pinfunction "6_6") (pintype "passive"))
      (node (ref "T69") (pin "1") (pinfunction "B_1") (pintype "passive"))
    )
    (net (code "94") (name "/6C") (class "Default")
      (node (ref "IC6") (pin "2") (pinfunction "QC_2") (pintype "tri_state"))
      (node (ref "RN60") (pin "2") (pinfunction "2_2") (pintype "passive"))
    )
    (net (code "95") (name "/6D") (class "Default")
      (node (ref "IC6") (pin "3") (pinfunction "QD_3") (pintype "tri_state"))
      (node (ref "RN60") (pin "1") (pinfunction "1_1") (pintype "passive"))
    )
    (net (code "96") (name "/6E") (class "Default")
      (node (ref "IC6") (pin "4") (pinfunction "QE_4") (pintype "tri_state"))
      (node (ref "RN61") (pin "4") (pinfunction "4_4") (pintype "passive"))
    )
    (net (code "97") (name "/6F") (class "Default")
      (node (ref "IC6") (pin "5") (pinfunction "QF_5") (pintype "tri_state"))
      (node (ref "RN61") (pin "3") (pinfunction "3_3") (pintype "passive"))
    )
    (net (code "98") (name "/6G") (class "Default")
      (node (ref "IC6") (pin "6") (pinfunction "QG_6") (pintype "tri_state"))
      (node (ref "RN61") (pin "2") (pinfunction "2_2") (pintype "passive"))
    )
    (net (code "99") (name "/6H") (class "Default")
      (node (ref "IC6") (pin "7") (pinfunction "QH_7") (pintype "tri_state"))
      (node (ref "RN61") (pin "1") (pinfunction "1_1") (pintype "passive"))
    )
    (net (code "100") (name "/7A") (class "Default")
      (node (ref "IC7") (pin "15") (pinfunction "QA_15") (pintype "tri_state"))
      (node (ref "RN70") (pin "4") (pinfunction "4_4") (pintype "passive"))
    )
    (net (code "101") (name "/7B") (class "Default")
      (node (ref "IC7") (pin "1") (pinfunction "QB_1") (pintype "tri_state"))
      (node (ref "RN70") (pin "3") (pinfunction "3_3") (pintype "passive"))
    )
    (net (code "102") (name "/7C") (class "Default")
      (node (ref "IC7") (pin "2") (pinfunction "QC_2") (pintype "tri_state"))
      (node (ref "RN70") (pin "2") (pinfunction "2_2") (pintype "passive"))
    )
    (net (code "103") (name "/7D") (class "Default")
      (node (ref "IC7") (pin "3") (pinfunction "QD_3") (pintype "tri_state"))
      (node (ref "RN70") (pin "1") (pinfunction "1_1") (pintype "passive"))
    )
    (net (code "104") (name "/7E") (class "Default")
      (node (ref "IC7") (pin "4") (pinfunction "QE_4") (pintype "tri_state"))
      (node (ref "RN71") (pin "4") (pinfunction "4_4") (pintype "passive"))
    )
    (net (code "105") (name "/7F") (class "Default")
      (node (ref "IC7") (pin "5") (pinfunction "QF_5") (pintype "tri_state"))
      (node (ref "RN71") (pin "3") (pinfunction "3_3") (pintype "passive"))
    )
    (net (code "106") (name "/7G") (class "Default")
      (node (ref "IC7") (pin "6") (pinfunction "QG_6") (pintype "tri_state"))
      (node (ref "RN71") (pin "2") (pinfunction "2_2") (pintype "passive"))
    )
    (net (code "107") (name "/7H") (class "Default")
      (node (ref "IC7") (pin "7") (pinfunction "QH_7") (pintype "tri_state"))
      (node (ref "RN71") (pin "1") (pinfunction "1_1") (pintype "passive"))
    )
    (net (code "108") (name "/8A") (class "Default")
      (node (ref "IC8") (pin "15") (pinfunction "QA_15") (pintype "tri_state"))
      (node (ref "RN80") (pin "4") (pinfunction "4_4") (pintype "passive"))
    )
    (net (code "109") (name "/8B") (class "Default")
      (node (ref "IC8") (pin "1") (pinfunction "QB_1") (pintype "tri_state"))
      (node (ref "RN80") (pin "3") (pinfunction "3_3") (pintype "passive"))
    )
    (net (code "110") (name "/8C") (class "Default")
      (node (ref "IC8") (pin "2") (pinfunction "QC_2") (pintype "tri_state"))
      (node (ref "RN80") (pin "2") (pinfunction "2_2") (pintype "passive"))
    )
    (net (code "111") (name "/8D") (class "Default")
      (node (ref "IC8") (pin "3") (pinfunction "QD_3") (pintype "tri_state"))
      (node (ref "RN80") (pin "1") (pinfunction "1_1") (pintype "passive"))
    )
    (net (code "112") (name "/8E") (class "Default")
      (node (ref "IC8") (pin "4") (pinfunction "QE_4") (pintype "tri_state"))
      (node (ref "RN81") (pin "4") (pinfunction "4_4") (pintype "passive"))
    )
    (net (code "113") (name "/8F") (class "Default")
      (node (ref "IC8") (pin "5") (pinfunction "QF_5") (pintype "tri_state"))
      (node (ref "RN81") (pin "3") (pinfunction "3_3") (pintype "passive"))
    )
    (net (code "114") (name "/8G") (class "Default")
      (node (ref "IC8") (pin "6") (pinfunction "QG_6") (pintype "tri_state"))
      (node (ref "RN81") (pin "2") (pinfunction "2_2") (pintype "passive"))
    )
    (net (code "115") (name "/8H") (class "Default")
      (node (ref "IC8") (pin "7") (pinfunction "QH_7") (pintype "tri_state"))
      (node (ref "RN81") (pin "1") (pinfunction "1_1") (pintype "passive"))
    )
    (net (code "116") (name "/EN") (class "Default")
      (node (ref "IC1") (pin "13") (pinfunction "G_13") (pintype "input"))
      (node (ref "IC2") (pin "13") (pinfunction "G_13") (pintype "input"))
      (node (ref "IC3") (pin "13") (pinfunction "G_13") (pintype "input"))
      (node (ref "IC4") (pin "13") (pinfunction "G_13") (pintype "input"))
      (node (ref "IC5") (pin "13") (pinfunction "G_13") (pintype "input"))
      (node (ref "IC6") (pin "13") (pinfunction "G_13") (pintype "input"))
      (node (ref "IC7") (pin "13") (pinfunction "G_13") (pintype "input"))
      (node (ref "IC8") (pin "13") (pinfunction "G_13") (pintype "input"))
      (node (ref "JP1") (pin "1") (pinfunction "1_1") (pintype "passive"))
    )
    (net (code "117") (name "/GL1") (class "Default")
      (node (ref "RN31") (pin "5") (pinfunction "5_5") (pintype "passive"))
      (node (ref "T1") (pin "1") (pinfunction "B_1") (pintype "passive"))
    )
    (net (code "118") (name "/GL2") (class "Default")
      (node (ref "RN31") (pin "6") (pinfunction "6_6") (pintype "passive"))
      (node (ref "T2") (pin "1") (pinfunction "B_1") (pintype "passive"))
    )
    (net (code "119") (name "/GL3") (class "Default")
      (node (ref "RN60") (pin "7") (pinfunction "7_7") (pintype "passive"))
      (node (ref "T3") (pin "1") (pinfunction "B_1") (pintype "passive"))
    )
    (net (code "120") (name "/GL4") (class "Default")
      (node (ref "RN60") (pin "8") (pinfunction "8_8") (pintype "passive"))
      (node (ref "T4") (pin "1") (pinfunction "B_1") (pintype "passive"))
    )
    (net (code "121") (name "/MOSI") (class "Default")
      (node (ref "IC1") (pin "14") (pinfunction "SER_14") (pintype "input"))
      (node (ref "JP1") (pin "4") (pinfunction "4_4") (pintype "passive"))
    )
    (net (code "122") (name "/N1_B0") (class "Default")
      (node (ref "RN20") (pin "6") (pinfunction "6_6") (pintype "passive"))
      (node (ref "T11") (pin "1") (pinfunction "B_1") (pintype "passive"))
    )
    (net (code "123") (name "/N1_B1") (class "Default")
      (node (ref "RN10") (pin "5") (pinfunction "5_5") (pintype "passive"))
      (node (ref "T12") (pin "1") (pinfunction "B_1") (pintype "passive"))
    )
    (net (code "124") (name "/N1_B2") (class "Default")
      (node (ref "RN10") (pin "6") (pinfunction "6_6") (pintype "passive"))
      (node (ref "T13") (pin "1") (pinfunction "B_1") (pintype "passive"))
    )
    (net (code "125") (name "/N1_B3") (class "Default")
      (node (ref "RN10") (pin "7") (pinfunction "7_7") (pintype "passive"))
      (node (ref "T14") (pin "1") (pinfunction "B_1") (pintype "passive"))
    )
    (net (code "126") (name "/N1_B4") (class "Default")
      (node (ref "RN10") (pin "8") (pinfunction "8_8") (pintype "passive"))
      (node (ref "T15") (pin "1") (pinfunction "B_1") (pintype "passive"))
    )
    (net (code "127") (name "/N1_B5") (class "Default")
      (node (ref "RN11") (pin "5") (pinfunction "5_5") (pintype "passive"))
      (node (ref "T16") (pin "1") (pinfunction "B_1") (pintype "passive"))
    )
    (net (code "128") (name "/N1_B6") (class "Default")
      (node (ref "RN11") (pin "6") (pinfunction "6_6") (pintype "passive"))
      (node (ref "T17") (pin "1") (pinfunction "B_1") (pintype "passive"))
    )
    (net (code "129") (name "/N1_B7") (class "Default")
      (node (ref "RN11") (pin "7") (pinfunction "7_7") (pintype "passive"))
      (node (ref "T18") (pin "1") (pinfunction "B_1") (pintype "passive"))
    )
    (net (code "130") (name "/N1_B8") (class "Default")
      (node (ref "RN11") (pin "8") (pinfunction "8_8") (pintype "passive"))
      (node (ref "T19") (pin "1") (pinfunction "B_1") (pintype "passive"))
    )
    (net (code "131") (name "/N1_B9") (class "Default")
      (node (ref "RN20") (pin "5") (pinfunction "5_5") (pintype "passive"))
      (node (ref "T10") (pin "1") (pinfunction "B_1") (pintype "passive"))
    )
    (net (code "132") (name "/N1_K0") (class "Default")
      (node (ref "T12") (pin "3") (pinfunction "C_3") (pintype "passive"))
      (node (ref "U$4") (pin "0") (pinfunction "0_0") (pintype "bidirectional"))
    )
    (net (code "133") (name "/N1_K1") (class "Default")
      (node (ref "T11") (pin "3") (pinfunction "C_3") (pintype "passive"))
      (node (ref "U$4") (pin "1") (pinfunction "1_1") (pintype "bidirectional"))
    )
    (net (code "134") (name "/N1_K2") (class "Default")
      (node (ref "T10") (pin "3") (pinfunction "C_3") (pintype "passive"))
      (node (ref "U$4") (pin "2") (pinfunction "2_2") (pintype "bidirectional"))
    )
    (net (code "135") (name "/N1_K3") (class "Default")
      (node (ref "T19") (pin "3") (pinfunction "C_3") (pintype "passive"))
      (node (ref "U$4") (pin "3") (pinfunction "3_3") (pintype "bidirectional"))
    )
    (net (code "136") (name "/N1_K4") (class "Default")
      (node (ref "T18") (pin "3") (pinfunction "C_3") (pintype "passive"))
      (node (ref "U$4") (pin "4") (pinfunction "4_4") (pintype "bidirectional"))
    )
    (net (code "137") (name "/N1_K5") (class "Default")
      (node (ref "T17") (pin "3") (pinfunction "C_3") (pintype "passive"))
      (node (ref "U$4") (pin "5") (pinfunction "5_5") (pintype "bidirectional"))
    )
    (net (code "138") (name "/N1_K6") (class "Default")
      (node (ref "T16") (pin "3") (pinfunction "C_3") (pintype "passive"))
      (node (ref "U$4") (pin "6") (pinfunction "6_6") (pintype "bidirectional"))
    )
    (net (code "139") (name "/N1_K7") (class "Default")
      (node (ref "T15") (pin "3") (pinfunction "C_3") (pintype "passive"))
      (node (ref "U$4") (pin "7") (pinfunction "7_7") (pintype "bidirectional"))
    )
    (net (code "140") (name "/N1_K8") (class "Default")
      (node (ref "T14") (pin "3") (pinfunction "C_3") (pintype "passive"))
      (node (ref "U$4") (pin "8") (pinfunction "8_8") (pintype "bidirectional"))
    )
    (net (code "141") (name "/N1_K9") (class "Default")
      (node (ref "T13") (pin "3") (pinfunction "C_3") (pintype "passive"))
      (node (ref "U$4") (pin "9") (pinfunction "9_9") (pintype "bidirectional"))
    )
    (net (code "142") (name "/N2_0") (class "Default")
      (node (ref "T22") (pin "3") (pinfunction "C_3") (pintype "passive"))
      (node (ref "U$5") (pin "0") (pinfunction "0_0") (pintype "bidirectional"))
    )
    (net (code "143") (name "/N2_1") (class "Default")
      (node (ref "T21") (pin "3") (pinfunction "C_3") (pintype "passive"))
      (node (ref "U$5") (pin "1") (pinfunction "1_1") (pintype "bidirectional"))
    )
    (net (code "144") (name "/N2_2") (class "Default")
      (node (ref "T20") (pin "3") (pinfunction "C_3") (pintype "passive"))
      (node (ref "U$5") (pin "2") (pinfunction "2_2") (pintype "bidirectional"))
    )
    (net (code "145") (name "/N2_3") (class "Default")
      (node (ref "T29") (pin "3") (pinfunction "C_3") (pintype "passive"))
      (node (ref "U$5") (pin "3") (pinfunction "3_3") (pintype "bidirectional"))
    )
    (net (code "146") (name "/N2_4") (class "Default")
      (node (ref "T28") (pin "3") (pinfunction "C_3") (pintype "passive"))
      (node (ref "U$5") (pin "4") (pinfunction "4_4") (pintype "bidirectional"))
    )
    (net (code "147") (name "/N2_5") (class "Default")
      (node (ref "T27") (pin "3") (pinfunction "C_3") (pintype "passive"))
      (node (ref "U$5") (pin "5") (pinfunction "5_5") (pintype "bidirectional"))
    )
    (net (code "148") (name "/N2_6") (class "Default")
      (node (ref "T26") (pin "3") (pinfunction "C_3") (pintype "passive"))
      (node (ref "U$5") (pin "6") (pinfunction "6_6") (pintype "bidirectional"))
    )
    (net (code "149") (name "/N2_7") (class "Default")
      (node (ref "T25") (pin "3") (pinfunction "C_3") (pintype "passive"))
      (node (ref "U$5") (pin "7") (pinfunction "7_7") (pintype "bidirectional"))
    )
    (net (code "150") (name "/N2_8") (class "Default")
      (node (ref "T24") (pin "3") (pinfunction "C_3") (pintype "passive"))
      (node (ref "U$5") (pin "8") (pinfunction "8_8") (pintype "bidirectional"))
    )
    (net (code "151") (name "/N2_9") (class "Default")
      (node (ref "T23") (pin "3") (pinfunction "C_3") (pintype "passive"))
      (node (ref "U$5") (pin "9") (pinfunction "9_9") (pintype "bidirectional"))
    )
    (net (code "152") (name "/N3_0") (class "Default")
      (node (ref "T32") (pin "3") (pinfunction "C_3") (pintype "passive"))
      (node (ref "U$6") (pin "0") (pinfunction "0_0") (pintype "bidirectional"))
    )
    (net (code "153") (name "/N3_1") (class "Default")
      (node (ref "T31") (pin "3") (pinfunction "C_3") (pintype "passive"))
      (node (ref "U$6") (pin "1") (pinfunction "1_1") (pintype "bidirectional"))
    )
    (net (code "154") (name "/N3_2") (class "Default")
      (node (ref "T30") (pin "3") (pinfunction "C_3") (pintype "passive"))
      (node (ref "U$6") (pin "2") (pinfunction "2_2") (pintype "bidirectional"))
    )
    (net (code "155") (name "/N3_3") (class "Default")
      (node (ref "T39") (pin "3") (pinfunction "C_3") (pintype "passive"))
      (node (ref "U$6") (pin "3") (pinfunction "3_3") (pintype "bidirectional"))
    )
    (net (code "156") (name "/N3_4") (class "Default")
      (node (ref "T38") (pin "3") (pinfunction "C_3") (pintype "passive"))
      (node (ref "U$6") (pin "4") (pinfunction "4_4") (pintype "bidirectional"))
    )
    (net (code "157") (name "/N3_5") (class "Default")
      (node (ref "T37") (pin "3") (pinfunction "C_3") (pintype "passive"))
      (node (ref "U$6") (pin "5") (pinfunction "5_5") (pintype "bidirectional"))
    )
    (net (code "158") (name "/N3_6") (class "Default")
      (node (ref "T36") (pin "3") (pinfunction "C_3") (pintype "passive"))
      (node (ref "U$6") (pin "6") (pinfunction "6_6") (pintype "bidirectional"))
    )
    (net (code "159") (name "/N3_7") (class "Default")
      (node (ref "T35") (pin "3") (pinfunction "C_3") (pintype "passive"))
      (node (ref "U$6") (pin "7") (pinfunction "7_7") (pintype "bidirectional"))
    )
    (net (code "160") (name "/N3_8") (class "Default")
      (node (ref "T34") (pin "3") (pinfunction "C_3") (pintype "passive"))
      (node (ref "U$6") (pin "8") (pinfunction "8_8") (pintype "bidirectional"))
    )
    (net (code "161") (name "/N3_9") (class "Default")
      (node (ref "T33") (pin "3") (pinfunction "C_3") (pintype "passive"))
      (node (ref "U$6") (pin "9") (pinfunction "9_9") (pintype "bidirectional"))
    )
    (net (code "162") (name "/N4_0") (class "Default")
      (node (ref "T42") (pin "3") (pinfunction "C_3") (pintype "passive"))
      (node (ref "U$7") (pin "0") (pinfunction "0_0") (pintype "bidirectional"))
    )
    (net (code "163") (name "/N4_1") (class "Default")
      (node (ref "T41") (pin "3") (pinfunction "C_3") (pintype "passive"))
      (node (ref "U$7") (pin "1") (pinfunction "1_1") (pintype "bidirectional"))
    )
    (net (code "164") (name "/N4_2") (class "Default")
      (node (ref "T40") (pin "3") (pinfunction "C_3") (pintype "passive"))
      (node (ref "U$7") (pin "2") (pinfunction "2_2") (pintype "bidirectional"))
    )
    (net (code "165") (name "/N4_3") (class "Default")
      (node (ref "T49") (pin "3") (pinfunction "C_3") (pintype "passive"))
      (node (ref "U$7") (pin "3") (pinfunction "3_3") (pintype "bidirectional"))
    )
    (net (code "166") (name "/N4_4") (class "Default")
      (node (ref "T48") (pin "3") (pinfunction "C_3") (pintype "passive"))
      (node (ref "U$7") (pin "4") (pinfunction "4_4") (pintype "bidirectional"))
    )
    (net (code "167") (name "/N4_5") (class "Default")
      (node (ref "T47") (pin "3") (pinfunction "C_3") (pintype "passive"))
      (node (ref "U$7") (pin "5") (pinfunction "5_5") (pintype "bidirectional"))
    )
    (net (code "168") (name "/N4_6") (class "Default")
      (node (ref "T46") (pin "3") (pinfunction "C_3") (pintype "passive"))
      (node (ref "U$7") (pin "6") (pinfunction "6_6") (pintype "bidirectional"))
    )
    (net (code "169") (name "/N4_7") (class "Default")
      (node (ref "T45") (pin "3") (pinfunction "C_3") (pintype "passive"))
      (node (ref "U$7") (pin "7") (pinfunction "7_7") (pintype "bidirectional"))
    )
    (net (code "170") (name "/N4_8") (class "Default")
      (node (ref "T44") (pin "3") (pinfunction "C_3") (pintype "passive"))
      (node (ref "U$7") (pin "8") (pinfunction "8_8") (pintype "bidirectional"))
    )
    (net (code "171") (name "/N4_9") (class "Default")
      (node (ref "T43") (pin "3") (pinfunction "C_3") (pintype "passive"))
      (node (ref "U$7") (pin "9") (pinfunction "9_9") (pintype "bidirectional"))
    )
    (net (code "172") (name "/N5_0") (class "Default")
      (node (ref "T52") (pin "3") (pinfunction "C_3") (pintype "passive"))
      (node (ref "U$8") (pin "0") (pinfunction "0_0") (pintype "bidirectional"))
    )
    (net (code "173") (name "/N5_1") (class "Default")
      (node (ref "T51") (pin "3") (pinfunction "C_3") (pintype "passive"))
      (node (ref "U$8") (pin "1") (pinfunction "1_1") (pintype "bidirectional"))
    )
    (net (code "174") (name "/N5_2") (class "Default")
      (node (ref "T50") (pin "3") (pinfunction "C_3") (pintype "passive"))
      (node (ref "U$8") (pin "2") (pinfunction "2_2") (pintype "bidirectional"))
    )
    (net (code "175") (name "/N5_3") (class "Default")
      (node (ref "T59") (pin "3") (pinfunction "C_3") (pintype "passive"))
      (node (ref "U$8") (pin "3") (pinfunction "3_3") (pintype "bidirectional"))
    )
    (net (code "176") (name "/N5_4") (class "Default")
      (node (ref "T58") (pin "3") (pinfunction "C_3") (pintype "passive"))
      (node (ref "U$8") (pin "4") (pinfunction "4_4") (pintype "bidirectional"))
    )
    (net (code "177") (name "/N5_5") (class "Default")
      (node (ref "T57") (pin "3") (pinfunction "C_3") (pintype "passive"))
      (node (ref "U$8") (pin "5") (pinfunction "5_5") (pintype "bidirectional"))
    )
    (net (code "178") (name "/N5_6") (class "Default")
      (node (ref "T56") (pin "3") (pinfunction "C_3") (pintype "passive"))
      (node (ref "U$8") (pin "6") (pinfunction "6_6") (pintype "bidirectional"))
    )
    (net (code "179") (name "/N5_7") (class "Default")
      (node (ref "T55") (pin "3") (pinfunction "C_3") (pintype "passive"))
      (node (ref "U$8") (pin "7") (pinfunction "7_7") (pintype "bidirectional"))
    )
    (net (code "180") (name "/N5_8") (class "Default")
      (node (ref "T54") (pin "3") (pinfunction "C_3") (pintype "passive"))
      (node (ref "U$8") (pin "8") (pinfunction "8_8") (pintype "bidirectional"))
    )
    (net (code "181") (name "/N5_9") (class "Default")
      (node (ref "T53") (pin "3") (pinfunction "C_3") (pintype "passive"))
      (node (ref "U$8") (pin "9") (pinfunction "9_9") (pintype "bidirectional"))
    )
    (net (code "182") (name "/N6_0") (class "Default")
      (node (ref "T62") (pin "3") (pinfunction "C_3") (pintype "passive"))
      (node (ref "U$9") (pin "0") (pinfunction "0_0") (pintype "bidirectional"))
    )
    (net (code "183") (name "/N6_1") (class "Default")
      (node (ref "T61") (pin "3") (pinfunction "C_3") (pintype "passive"))
      (node (ref "U$9") (pin "1") (pinfunction "1_1") (pintype "bidirectional"))
    )
    (net (code "184") (name "/N6_2") (class "Default")
      (node (ref "T60") (pin "3") (pinfunction "C_3") (pintype "passive"))
      (node (ref "U$9") (pin "2") (pinfunction "2_2") (pintype "bidirectional"))
    )
    (net (code "185") (name "/N6_3") (class "Default")
      (node (ref "T69") (pin "3") (pinfunction "C_3") (pintype "passive"))
      (node (ref "U$9") (pin "3") (pinfunction "3_3") (pintype "bidirectional"))
    )
    (net (code "186") (name "/N6_4") (class "Default")
      (node (ref "T68") (pin "3") (pinfunction "C_3") (pintype "passive"))
      (node (ref "U$9") (pin "4") (pinfunction "4_4") (pintype "bidirectional"))
    )
    (net (code "187") (name "/N6_5") (class "Default")
      (node (ref "T67") (pin "3") (pinfunction "C_3") (pintype "passive"))
      (node (ref "U$9") (pin "5") (pinfunction "5_5") (pintype "bidirectional"))
    )
    (net (code "188") (name "/N6_6") (class "Default")
      (node (ref "T66") (pin "3") (pinfunction "C_3") (pintype "passive"))
      (node (ref "U$9") (pin "6") (pinfunction "6_6") (pintype "bidirectional"))
    )
    (net (code "189") (name "/N6_7") (class "Default")
      (node (ref "T65") (pin "3") (pinfunction "C_3") (pintype "passive"))
      (node (ref "U$9") (pin "7") (pinfunction "7_7") (pintype "bidirectional"))
    )
    (net (code "190") (name "/N6_8") (class "Default")
      (node (ref "T64") (pin "3") (pinfunction "C_3") (pintype "passive"))
      (node (ref "U$9") (pin "8") (pinfunction "8_8") (pintype "bidirectional"))
    )
    (net (code "191") (name "/N6_9") (class "Default")
      (node (ref "T63") (pin "3") (pinfunction "C_3") (pintype "passive"))
      (node (ref "U$9") (pin "9") (pinfunction "9_9") (pintype "bidirectional"))
    )
    (net (code "192") (name "/RCK") (class "Default")
      (node (ref "IC1") (pin "12") (pinfunction "RCK_12") (pintype "input"))
      (node (ref "IC2") (pin "12") (pinfunction "RCK_12") (pintype "input"))
      (node (ref "IC3") (pin "12") (pinfunction "RCK_12") (pintype "input"))
      (node (ref "IC4") (pin "12") (pinfunction "RCK_12") (pintype "input"))
      (node (ref "IC5") (pin "12") (pinfunction "RCK_12") (pintype "input"))
      (node (ref "IC6") (pin "12") (pinfunction "RCK_12") (pintype "input"))
      (node (ref "IC7") (pin "12") (pinfunction "RCK_12") (pintype "input"))
      (node (ref "IC8") (pin "12") (pinfunction "RCK_12") (pintype "input"))
      (node (ref "JP1") (pin "5") (pinfunction "5_5") (pintype "passive"))
    )
    (net (code "193") (name "/SCK") (class "Default")
      (node (ref "IC1") (pin "11") (pinfunction "SCK_11") (pintype "input"))
      (node (ref "IC2") (pin "11") (pinfunction "SCK_11") (pintype "input"))
      (node (ref "IC3") (pin "11") (pinfunction "SCK_11") (pintype "input"))
      (node (ref "IC4") (pin "11") (pinfunction "SCK_11") (pintype "input"))
      (node (ref "IC5") (pin "11") (pinfunction "SCK_11") (pintype "input"))
      (node (ref "IC6") (pin "11") (pinfunction "SCK_11") (pintype "input"))
      (node (ref "IC7") (pin "11") (pinfunction "SCK_11") (pintype "input"))
      (node (ref "IC8") (pin "11") (pinfunction "SCK_11") (pintype "input"))
      (node (ref "JP1") (pin "3") (pinfunction "3_3") (pintype "passive"))
    )
    (net (code "194") (name "/SCL") (class "Default")
      (node (ref "IC1") (pin "10") (pinfunction "SCL_10") (pintype "input"))
      (node (ref "IC2") (pin "10") (pinfunction "SCL_10") (pintype "input"))
      (node (ref "IC3") (pin "10") (pinfunction "SCL_10") (pintype "input"))
      (node (ref "IC4") (pin "10") (pinfunction "SCL_10") (pintype "input"))
      (node (ref "IC5") (pin "10") (pinfunction "SCL_10") (pintype "input"))
      (node (ref "IC6") (pin "10") (pinfunction "SCL_10") (pintype "input"))
      (node (ref "IC7") (pin "10") (pinfunction "SCL_10") (pintype "input"))
      (node (ref "IC8") (pin "10") (pinfunction "SCL_10") (pintype "input"))
      (node (ref "JP1") (pin "2") (pinfunction "2_2") (pintype "passive"))
    )
    (net (code "195") (name "GND") (class "Default")
      (node (ref "C1") (pin "2") (pinfunction "2_2") (pintype "passive"))
      (node (ref "C2") (pin "2") (pinfunction "2_2") (pintype "passive"))
      (node (ref "C3") (pin "2") (pinfunction "2_2") (pintype "passive"))
      (node (ref "C4") (pin "2") (pinfunction "2_2") (pintype "passive"))
      (node (ref "C5") (pin "2") (pinfunction "2_2") (pintype "passive"))
      (node (ref "C6") (pin "2") (pinfunction "2_2") (pintype "passive"))
      (node (ref "C7") (pin "2") (pinfunction "2_2") (pintype "passive"))
      (node (ref "C8") (pin "2") (pinfunction "2_2") (pintype "passive"))
      (node (ref "IC1") (pin "8") (pinfunction "GND_8") (pintype "power_in"))
      (node (ref "IC2") (pin "8") (pinfunction "GND_8") (pintype "power_in"))
      (node (ref "IC3") (pin "8") (pinfunction "GND_8") (pintype "power_in"))
      (node (ref "IC4") (pin "8") (pinfunction "GND_8") (pintype "power_in"))
      (node (ref "IC5") (pin "8") (pinfunction "GND_8") (pintype "power_in"))
      (node (ref "IC6") (pin "8") (pinfunction "GND_8") (pintype "power_in"))
      (node (ref "IC7") (pin "8") (pinfunction "GND_8") (pintype "power_in"))
      (node (ref "IC8") (pin "8") (pinfunction "GND_8") (pintype "power_in"))
      (node (ref "JP1") (pin "6") (pinfunction "6_6") (pintype "passive"))
      (node (ref "JP2") (pin "2") (pinfunction "2_2") (pintype "passive"))
      (node (ref "JP2") (pin "3") (pinfunction "3_3") (pintype "passive"))
      (node (ref "JP2") (pin "4") (pinfunction "4_4") (pintype "passive"))
      (node (ref "JP2") (pin "5") (pinfunction "5_5") (pintype "passive"))
      (node (ref "T1") (pin "2") (pinfunction "E_2") (pintype "passive"))
      (node (ref "T10") (pin "2") (pinfunction "E_2") (pintype "passive"))
      (node (ref "T11") (pin "2") (pinfunction "E_2") (pintype "passive"))
      (node (ref "T12") (pin "2") (pinfunction "E_2") (pintype "passive"))
      (node (ref "T13") (pin "2") (pinfunction "E_2") (pintype "passive"))
      (node (ref "T14") (pin "2") (pinfunction "E_2") (pintype "passive"))
      (node (ref "T15") (pin "2") (pinfunction "E_2") (pintype "passive"))
      (node (ref "T16") (pin "2") (pinfunction "E_2") (pintype "passive"))
      (node (ref "T17") (pin "2") (pinfunction "E_2") (pintype "passive"))
      (node (ref "T18") (pin "2") (pinfunction "E_2") (pintype "passive"))
      (node (ref "T19") (pin "2") (pinfunction "E_2") (pintype "passive"))
      (node (ref "T2") (pin "2") (pinfunction "E_2") (pintype "passive"))
      (node (ref "T20") (pin "2") (pinfunction "E_2") (pintype "passive"))
      (node (ref "T21") (pin "2") (pinfunction "E_2") (pintype "passive"))
      (node (ref "T22") (pin "2") (pinfunction "E_2") (pintype "passive"))
      (node (ref "T23") (pin "2") (pinfunction "E_2") (pintype "passive"))
      (node (ref "T24") (pin "2") (pinfunction "E_2") (pintype "passive"))
      (node (ref "T25") (pin "2") (pinfunction "E_2") (pintype "passive"))
      (node (ref "T26") (pin "2") (pinfunction "E_2") (pintype "passive"))
      (node (ref "T27") (pin "2") (pinfunction "E_2") (pintype "passive"))
      (node (ref "T28") (pin "2") (pinfunction "E_2") (pintype "passive"))
      (node (ref "T29") (pin "2") (pinfunction "E_2") (pintype "passive"))
      (node (ref "T3") (pin "2") (pinfunction "E_2") (pintype "passive"))
      (node (ref "T30") (pin "2") (pinfunction "E_2") (pintype "passive"))
      (node (ref "T31") (pin "2") (pinfunction "E_2") (pintype "passive"))
      (node (ref "T32") (pin "2") (pinfunction "E_2") (pintype "passive"))
      (node (ref "T33") (pin "2") (pinfunction "E_2") (pintype "passive"))
      (node (ref "T34") (pin "2") (pinfunction "E_2") (pintype "passive"))
      (node (ref "T35") (pin "2") (pinfunction "E_2") (pintype "passive"))
      (node (ref "T36") (pin "2") (pinfunction "E_2") (pintype "passive"))
      (node (ref "T37") (pin "2") (pinfunction "E_2") (pintype "passive"))
      (node (ref "T38") (pin "2") (pinfunction "E_2") (pintype "passive"))
      (node (ref "T39") (pin "2") (pinfunction "E_2") (pintype "passive"))
      (node (ref "T4") (pin "2") (pinfunction "E_2") (pintype "passive"))
      (node (ref "T40") (pin "2") (pinfunction "E_2") (pintype "passive"))
      (node (ref "T41") (pin "2") (pinfunction "E_2") (pintype "passive"))
      (node (ref "T42") (pin "2") (pinfunction "E_2") (pintype "passive"))
      (node (ref "T43") (pin "2") (pinfunction "E_2") (pintype "passive"))
      (node (ref "T44") (pin "2") (pinfunction "E_2") (pintype "passive"))
      (node (ref "T45") (pin "2") (pinfunction "E_2") (pintype "passive"))
      (node (ref "T46") (pin "2") (pinfunction "E_2") (pintype "passive"))
      (node (ref "T47") (pin "2") (pinfunction "E_2") (pintype "passive"))
      (node (ref "T48") (pin "2") (pinfunction "E_2") (pintype "passive"))
      (node (ref "T49") (pin "2") (pinfunction "E_2") (pintype "passive"))
      (node (ref "T50") (pin "2") (pinfunction "E_2") (pintype "passive"))
      (node (ref "T51") (pin "2") (pinfunction "E_2") (pintype "passive"))
      (node (ref "T52") (pin "2") (pinfunction "E_2") (pintype "passive"))
      (node (ref "T53") (pin "2") (pinfunction "E_2") (pintype "passive"))
      (node (ref "T54") (pin "2") (pinfunction "E_2") (pintype "passive"))
      (node (ref "T55") (pin "2") (pinfunction "E_2") (pintype "passive"))
      (node (ref "T56") (pin "2") (pinfunction "E_2") (pintype "passive"))
      (node (ref "T57") (pin "2") (pinfunction "E_2") (pintype "passive"))
      (node (ref "T58") (pin "2") (pinfunction "E_2") (pintype "passive"))
      (node (ref "T59") (pin "2") (pinfunction "E_2") (pintype "passive"))
      (node (ref "T60") (pin "2") (pinfunction "E_2") (pintype "passive"))
      (node (ref "T61") (pin "2") (pinfunction "E_2") (pintype "passive"))
      (node (ref "T62") (pin "2") (pinfunction "E_2") (pintype "passive"))
      (node (ref "T63") (pin "2") (pinfunction "E_2") (pintype "passive"))
      (node (ref "T64") (pin "2") (pinfunction "E_2") (pintype "passive"))
      (node (ref "T65") (pin "2") (pinfunction "E_2") (pintype "passive"))
      (node (ref "T66") (pin "2") (pinfunction "E_2") (pintype "passive"))
      (node (ref "T67") (pin "2") (pinfunction "E_2") (pintype "passive"))
      (node (ref "T68") (pin "2") (pinfunction "E_2") (pintype "passive"))
      (node (ref "T69") (pin "2") (pinfunction "E_2") (pintype "passive"))
    )
    (net (code "196") (name "Net-(GL1-A)") (class "Default")
      (node (ref "GL1") (pin "1") (pinfunction "A_1") (pintype "passive"))
      (node (ref "R1") (pin "1") (pinfunction "1_1") (pintype "passive"))
    )
    (net (code "197") (name "Net-(GL1-A1)") (class "Default")
      (node (ref "GL1") (pin "2") (pinfunction "A1_2") (pintype "passive"))
      (node (ref "T1") (pin "3") (pinfunction "C_3") (pintype "passive"))
    )
    (net (code "198") (name "Net-(GL2-A)") (class "Default")
      (node (ref "GL2") (pin "1") (pinfunction "A_1") (pintype "passive"))
      (node (ref "R2") (pin "1") (pinfunction "1_1") (pintype "passive"))
    )
    (net (code "199") (name "Net-(GL2-A1)") (class "Default")
      (node (ref "GL2") (pin "2") (pinfunction "A1_2") (pintype "passive"))
      (node (ref "T2") (pin "3") (pinfunction "C_3") (pintype "passive"))
    )
    (net (code "200") (name "Net-(GL3-A)") (class "Default")
      (node (ref "GL3") (pin "1") (pinfunction "A_1") (pintype "passive"))
      (node (ref "R3") (pin "1") (pinfunction "1_1") (pintype "passive"))
    )
    (net (code "201") (name "Net-(GL3-A1)") (class "Default")
      (node (ref "GL3") (pin "2") (pinfunction "A1_2") (pintype "passive"))
      (node (ref "T3") (pin "3") (pinfunction "C_3") (pintype "passive"))
    )
    (net (code "202") (name "Net-(GL4-A)") (class "Default")
      (node (ref "GL4") (pin "1") (pinfunction "A_1") (pintype "passive"))
      (node (ref "R4") (pin "1") (pinfunction "1_1") (pintype "passive"))
    )
    (net (code "203") (name "Net-(GL4-A1)") (class "Default")
      (node (ref "GL4") (pin "2") (pinfunction "A1_2") (pintype "passive"))
      (node (ref "T4") (pin "3") (pinfunction "C_3") (pintype "passive"))
    )
    (net (code "204") (name "Net-(IC1A-QH*)") (class "Default")
      (node (ref "IC1") (pin "9") (pinfunction "QH*_9") (pintype "tri_state"))
      (node (ref "IC2") (pin "14") (pinfunction "SER_14") (pintype "input"))
    )
    (net (code "205") (name "Net-(IC2A-QH*)") (class "Default")
      (node (ref "IC2") (pin "9") (pinfunction "QH*_9") (pintype "tri_state"))
      (node (ref "IC3") (pin "14") (pinfunction "SER_14") (pintype "input"))
    )
    (net (code "206") (name "Net-(IC3A-QH*)") (class "Default")
      (node (ref "IC3") (pin "9") (pinfunction "QH*_9") (pintype "tri_state"))
      (node (ref "IC4") (pin "14") (pinfunction "SER_14") (pintype "input"))
    )
    (net (code "207") (name "Net-(IC4A-QH*)") (class "Default")
      (node (ref "IC4") (pin "9") (pinfunction "QH*_9") (pintype "tri_state"))
      (node (ref "IC5") (pin "14") (pinfunction "SER_14") (pintype "input"))
    )
    (net (code "208") (name "Net-(IC5A-QH*)") (class "Default")
      (node (ref "IC5") (pin "9") (pinfunction "QH*_9") (pintype "tri_state"))
      (node (ref "IC6") (pin "14") (pinfunction "SER_14") (pintype "input"))
    )
    (net (code "209") (name "Net-(IC6A-QH*)") (class "Default")
      (node (ref "IC6") (pin "9") (pinfunction "QH*_9") (pintype "tri_state"))
      (node (ref "IC7") (pin "14") (pinfunction "SER_14") (pintype "input"))
    )
    (net (code "210") (name "Net-(IC7A-QH*)") (class "Default")
      (node (ref "IC7") (pin "9") (pinfunction "QH*_9") (pintype "tri_state"))
      (node (ref "IC8") (pin "14") (pinfunction "SER_14") (pintype "input"))
    )
    (net (code "211") (name "Net-(U$4-A1)") (class "Default")
      (node (ref "R10") (pin "1") (pinfunction "1_1") (pintype "passive"))
      (node (ref "U$4") (pin "A") (pinfunction "A1_A") (pintype "bidirectional"))
    )
    (net (code "212") (name "Net-(U$5-A1)") (class "Default")
      (node (ref "R20") (pin "1") (pinfunction "1_1") (pintype "passive"))
      (node (ref "U$5") (pin "A") (pinfunction "A1_A") (pintype "bidirectional"))
    )
    (net (code "213") (name "Net-(U$6-A1)") (class "Default")
      (node (ref "R30") (pin "1") (pinfunction "1_1") (pintype "passive"))
      (node (ref "U$6") (pin "A") (pinfunction "A1_A") (pintype "bidirectional"))
    )
    (net (code "214") (name "Net-(U$7-A1)") (class "Default")
      (node (ref "R40") (pin "1") (pinfunction "1_1") (pintype "passive"))
      (node (ref "U$7") (pin "A") (pinfunction "A1_A") (pintype "bidirectional"))
    )
    (net (code "215") (name "Net-(U$8-A1)") (class "Default")
      (node (ref "R50") (pin "1") (pinfunction "1_1") (pintype "passive"))
      (node (ref "U$8") (pin "A") (pinfunction "A1_A") (pintype "bidirectional"))
    )
    (net (code "216") (name "Net-(U$9-A1)") (class "Default")
      (node (ref "R60") (pin "1") (pinfunction "1_1") (pintype "passive"))
      (node (ref "U$9") (pin "A") (pinfunction "A1_A") (pintype "bidirectional"))
    )
    (net (code "217") (name "VDD") (class "Default")
      (node (ref "JP2") (pin "1") (pinfunction "1_1") (pintype "passive"))
      (node (ref "R1") (pin "2") (pinfunction "2_2") (pintype "passive"))
      (node (ref "R10") (pin "2") (pinfunction "2_2") (pintype "passive"))
      (node (ref "R2") (pin "2") (pinfunction "2_2") (pintype "passive"))
      (node (ref "R20") (pin "2") (pinfunction "2_2") (pintype "passive"))
      (node (ref "R3") (pin "2") (pinfunction "2_2") (pintype "passive"))
      (node (ref "R30") (pin "2") (pinfunction "2_2") (pintype "passive"))
      (node (ref "R4") (pin "2") (pinfunction "2_2") (pintype "passive"))
      (node (ref "R40") (pin "2") (pinfunction "2_2") (pintype "passive"))
      (node (ref "R50") (pin "2") (pinfunction "2_2") (pintype "passive"))
      (node (ref "R60") (pin "2") (pinfunction "2_2") (pintype "passive"))
    )
    (net (code "218") (name "unconnected-(IC8A-QH*-Pad9)") (class "Default")
      (node (ref "IC8") (pin "9") (pinfunction "QH*_9") (pintype "tri_state"))
    )
    (net (code "219") (name "unconnected-(U$4-DP-Pad.)") (class "Default")
      (node (ref "U$4") (pin ".") (pinfunction "DP_.") (pintype "bidirectional"))
    )
    (net (code "220") (name "unconnected-(U$5-DP-Pad.)") (class "Default")
      (node (ref "U$5") (pin ".") (pinfunction "DP_.") (pintype "bidirectional"))
    )
    (net (code "221") (name "unconnected-(U$6-DP-Pad.)") (class "Default")
      (node (ref "U$6") (pin ".") (pinfunction "DP_.") (pintype "bidirectional"))
    )
    (net (code "222") (name "unconnected-(U$7-DP-Pad.)") (class "Default")
      (node (ref "U$7") (pin ".") (pinfunction "DP_.") (pintype "bidirectional"))
    )
    (net (code "223") (name "unconnected-(U$8-DP-Pad.)") (class "Default")
      (node (ref "U$8") (pin ".") (pinfunction "DP_.") (pintype "bidirectional"))
    )
    (net (code "224") (name "unconnected-(U$9-DP-Pad.)") (class "Default")
      (node (ref "U$9") (pin ".") (pinfunction "DP_.") (pintype "bidirectional"))
    )
  )
)
